# MercurialSDR_MISC.net
KiCad netlist of a schematic drawn in Altium Designer
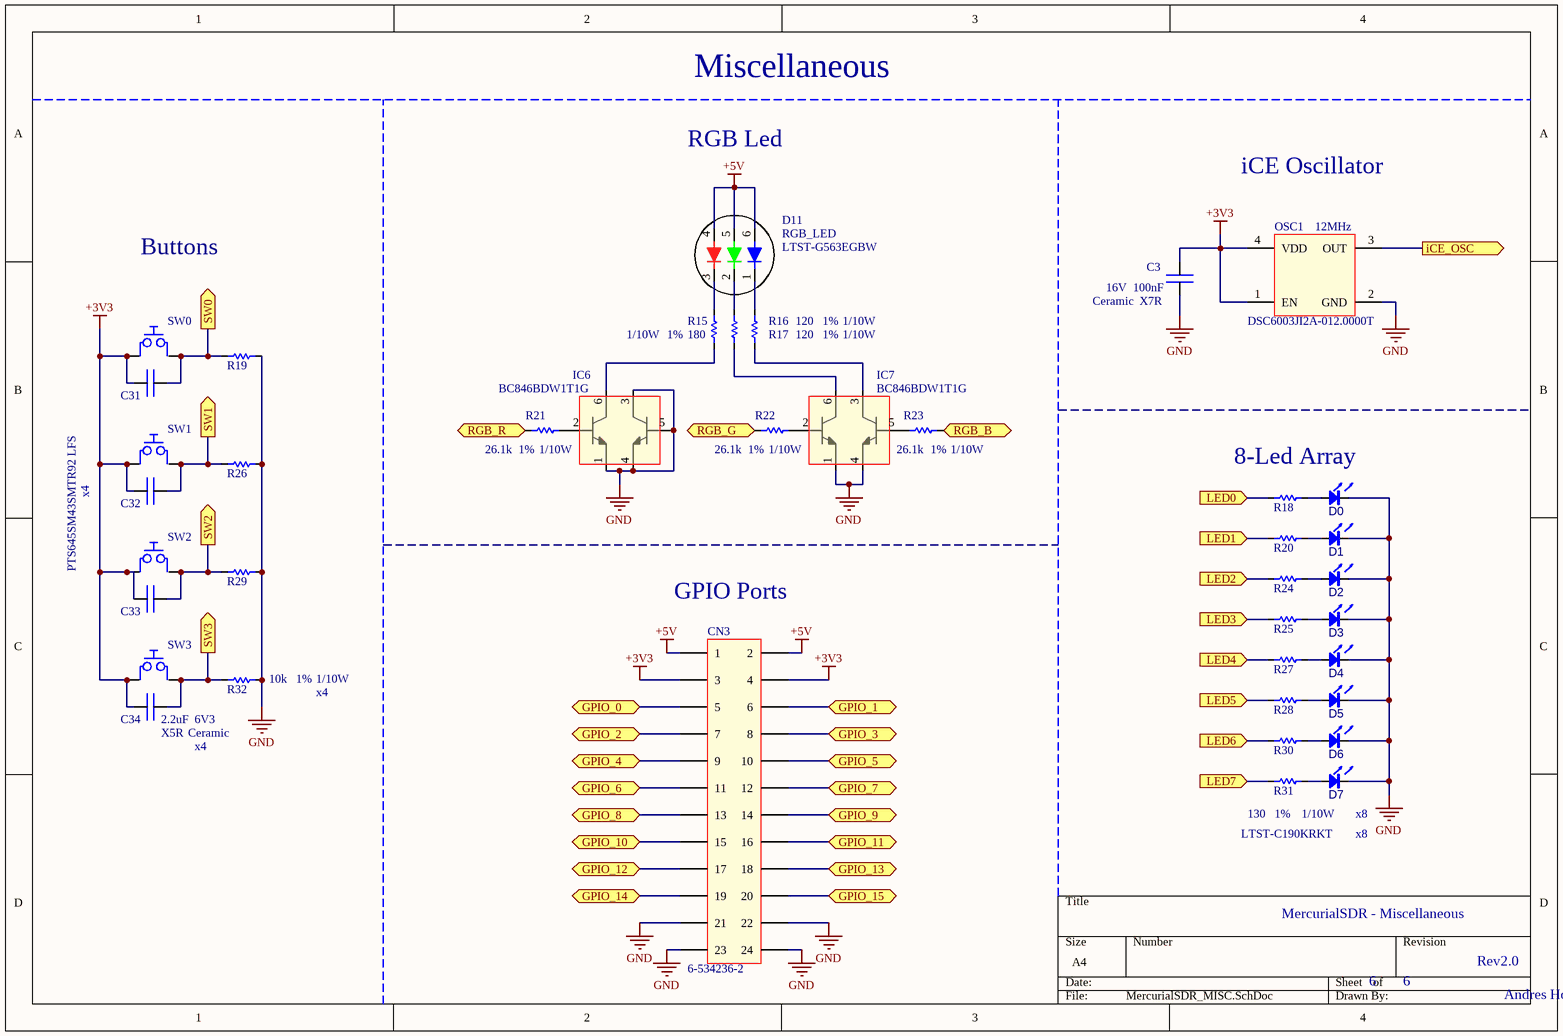
[diagram p0: MercurialSDR_MISC.SchDoc]

(export (version "E")
  (design (tool "Eeschema 10.0.6"))
  (components
    (comp (ref "C3")
      (value "100nF")
      (footprint "CAP_0603")
      (description "Capacitor no polarizado")
      (fields
        (field (name "TEMP COEF") "X7R")
        (field (name "PART NUMBER") "CL10B104KO8NNNC")
        (field (name "VR") "16V")
        (field (name "MATERIAL") "Ceramic")
        (field (name "Comment") "Capacitor")
      )
      (libsource (lib "MercurialSDR") (part "Cap"))
    )
    (comp (ref "C31")
      (value "Capacitor")
      (footprint "CAP_0603")
      (description "Capacitor no polarizado")
      (fields (field (name "PART NUMBER") "CL10A225KQ8NNNC"))
      (libsource (lib "MercurialSDR") (part "Cap"))
    )
    (comp (ref "C32")
      (value "Capacitor")
      (footprint "CAP_0603")
      (description "Capacitor no polarizado")
      (fields (field (name "PART NUMBER") "CL10A225KQ8NNNC"))
      (libsource (lib "MercurialSDR") (part "Cap"))
    )
    (comp (ref "C33")
      (value "Capacitor")
      (footprint "CAP_0603")
      (description "Capacitor no polarizado")
      (fields (field (name "PART NUMBER") "CL10A225KQ8NNNC"))
      (libsource (lib "MercurialSDR") (part "Cap"))
    )
    (comp (ref "C34")
      (value "2.2uF")
      (footprint "CAP_0603")
      (description "Capacitor no polarizado")
      (fields
        (field (name "TEMP COEF") "X5R")
        (field (name "PART NUMBER") "CL10A225KQ8NNNC")
        (field (name "VR") "6V3")
        (field (name "MATERIAL") "Ceramic")
        (field (name "Comment") "Capacitor")
      )
      (libsource (lib "MercurialSDR") (part "Cap"))
    )
    (comp (ref "CN3")
      (value "Connector")
      (footprint "CON_12x2")
      (description "Conector genérico 12x2")
      (fields (field (name "PART NUMBER") "6-534236-2"))
      (libsource (lib "MercurialSDR") (part "CN_12x2"))
    )
    (comp (ref "D0")
      (value "Led_small")
      (footprint "LED_0603")
      (fields (field (name "PART NUMBER") "LTST-C190KRKT"))
      (libsource (lib "MercurialSDR") (part "Led_small"))
    )
    (comp (ref "D1")
      (value "Led_small")
      (footprint "LED_0603")
      (fields (field (name "PART NUMBER") "LTST-C190KRKT"))
      (libsource (lib "MercurialSDR") (part "Led_small"))
    )
    (comp (ref "D2")
      (value "Led_small")
      (footprint "LED_0603")
      (fields (field (name "PART NUMBER") "LTST-C190KRKT"))
      (libsource (lib "MercurialSDR") (part "Led_small"))
    )
    (comp (ref "D3")
      (value "Led_small")
      (footprint "LED_0603")
      (fields (field (name "PART NUMBER") "LTST-C190KRKT"))
      (libsource (lib "MercurialSDR") (part "Led_small"))
    )
    (comp (ref "D4")
      (value "Led_small")
      (footprint "LED_0603")
      (fields (field (name "PART NUMBER") "LTST-C190KRKT"))
      (libsource (lib "MercurialSDR") (part "Led_small"))
    )
    (comp (ref "D5")
      (value "Led_small")
      (footprint "LED_0603")
      (fields (field (name "PART NUMBER") "LTST-C190KRKT"))
      (libsource (lib "MercurialSDR") (part "Led_small"))
    )
    (comp (ref "D6")
      (value "Led_small")
      (footprint "LED_0603")
      (fields (field (name "PART NUMBER") "LTST-C190KRKT"))
      (libsource (lib "MercurialSDR") (part "Led_small"))
    )
    (comp (ref "D7")
      (value "Led_small")
      (footprint "LED_0603")
      (fields (field (name "PART NUMBER") "LTST-C190KRKT"))
      (libsource (lib "MercurialSDR") (part "Led_small"))
    )
    (comp (ref "D11")
      (value "RGB_LED")
      (footprint "LED_RGB 5x5mm")
      (description "Led RGB")
      (fields (field (name "PART NUMBER") "LTST-G563EGBW"))
      (libsource (lib "MercurialSDR") (part "LED_RGB"))
    )
    (comp (ref "IC6")
      (value "BC846")
      (footprint "TSSOP-6")
      (description "TBJ NPN Dual")
      (fields (field (name "PART NUMBER") "BC846BDW1T1G"))
      (libsource (lib "MercurialSDR") (part "BC846BDW_1"))
    )
    (comp (ref "IC7")
      (value "BC846")
      (footprint "TSSOP-6")
      (description "TBJ NPN Dual")
      (fields (field (name "PART NUMBER") "BC846BDW1T1G"))
      (libsource (lib "MercurialSDR") (part "BC846BDW_1"))
    )
    (comp (ref "OSC1")
      (value "Oscillator")
      (footprint "VFLGA_2.5x2.0")
      (description "Oscilador de 4 terminales")
      (fields (field (name "PART NUMBER") "DSC6003JI2A-012.0000T") (field (name "FREQUENCY") "12MHz"))
      (libsource (lib "MercurialSDR") (part "Oscillator"))
    )
    (comp (ref "R15")
      (value "180")
      (footprint "RES_0603")
      (description "Resistor")
      (fields
        (field (name "POWER") "1/10W")
        (field (name "PART NUMBER") "CR0603-FX-1800ELF")
        (field (name "TOLERANCE") "1%")
        (field (name "Comment") "Resistor SMD")
      )
      (libsource (lib "MercurialSDR") (part "Res"))
    )
    (comp (ref "R16")
      (value "120")
      (footprint "RES_0603")
      (description "Resistor")
      (fields
        (field (name "POWER") "1/10W")
        (field (name "PART NUMBER") "CR0603-FX-1200ELF")
        (field (name "TOLERANCE") "1%")
        (field (name "Comment") "Resistor SMD")
      )
      (libsource (lib "MercurialSDR") (part "Res"))
    )
    (comp (ref "R17")
      (value "120")
      (footprint "RES_0603")
      (description "Resistor")
      (fields
        (field (name "POWER") "1/10W")
        (field (name "PART NUMBER") "CR0603-FX-1200ELF")
        (field (name "TOLERANCE") "1%")
        (field (name "Comment") "Resistor SMD")
      )
      (libsource (lib "MercurialSDR") (part "Res"))
    )
    (comp (ref "R18")
      (value "Resistor SMD")
      (footprint "RES_0603")
      (description "Resistor")
      (fields (field (name "POWER") "1/10W") (field (name "PART NUMBER") "CR0603-FX-1300ELF"))
      (libsource (lib "MercurialSDR") (part "Res"))
    )
    (comp (ref "R19")
      (value "10k")
      (footprint "RES_0603")
      (description "Resistor")
      (fields
        (field (name "POWER") "1/10W")
        (field (name "PART NUMBER") "CR0603-FX-1002EAS")
        (field (name "TOLERANCE") "1%")
        (field (name "Comment") "Resistor SMD")
      )
      (libsource (lib "MercurialSDR") (part "Res"))
    )
    (comp (ref "R20")
      (value "Resistor SMD")
      (footprint "RES_0603")
      (description "Resistor")
      (fields (field (name "POWER") "1/10W") (field (name "PART NUMBER") "CR0603-FX-1300ELF"))
      (libsource (lib "MercurialSDR") (part "Res"))
    )
    (comp (ref "R21")
      (value "26.1k")
      (footprint "RES_0603")
      (description "Resistor")
      (fields
        (field (name "POWER") "1/10W")
        (field (name "PART NUMBER") "CR0603-FX-2612ELF")
        (field (name "TOLERANCE") "1%")
        (field (name "Comment") "Resistor SMD")
      )
      (libsource (lib "MercurialSDR") (part "Res"))
    )
    (comp (ref "R22")
      (value "26.1k")
      (footprint "RES_0603")
      (description "Resistor")
      (fields
        (field (name "POWER") "1/10W")
        (field (name "PART NUMBER") "CR0603-FX-2612ELF")
        (field (name "TOLERANCE") "1%")
        (field (name "Comment") "Resistor SMD")
      )
      (libsource (lib "MercurialSDR") (part "Res"))
    )
    (comp (ref "R23")
      (value "26.1k")
      (footprint "RES_0603")
      (description "Resistor")
      (fields
        (field (name "POWER") "1/10W")
        (field (name "PART NUMBER") "CR0603-FX-2612ELF")
        (field (name "TOLERANCE") "1%")
        (field (name "Comment") "Resistor SMD")
      )
      (libsource (lib "MercurialSDR") (part "Res"))
    )
    (comp (ref "R24")
      (value "Resistor SMD")
      (footprint "RES_0603")
      (description "Resistor")
      (fields (field (name "POWER") "1/10W") (field (name "PART NUMBER") "CR0603-FX-1300ELF"))
      (libsource (lib "MercurialSDR") (part "Res"))
    )
    (comp (ref "R25")
      (value "Resistor SMD")
      (footprint "RES_0603")
      (description "Resistor")
      (fields (field (name "POWER") "1/10W") (field (name "PART NUMBER") "CR0603-FX-1300ELF"))
      (libsource (lib "MercurialSDR") (part "Res"))
    )
    (comp (ref "R26")
      (value "Resistor SMD")
      (footprint "RES_0603")
      (description "Resistor")
      (fields (field (name "POWER") "1/10W") (field (name "PART NUMBER") "CR0603-FX-1002EAS"))
      (libsource (lib "MercurialSDR") (part "Res"))
    )
    (comp (ref "R27")
      (value "Resistor SMD")
      (footprint "RES_0603")
      (description "Resistor")
      (fields (field (name "POWER") "1/10W") (field (name "PART NUMBER") "CR0603-FX-1300ELF"))
      (libsource (lib "MercurialSDR") (part "Res"))
    )
    (comp (ref "R28")
      (value "Resistor SMD")
      (footprint "RES_0603")
      (description "Resistor")
      (fields (field (name "POWER") "1/10W") (field (name "PART NUMBER") "CR0603-FX-1300ELF"))
      (libsource (lib "MercurialSDR") (part "Res"))
    )
    (comp (ref "R29")
      (value "Resistor SMD")
      (footprint "RES_0603")
      (description "Resistor")
      (fields (field (name "POWER") "1/10W") (field (name "PART NUMBER") "CR0603-FX-1002EAS"))
      (libsource (lib "MercurialSDR") (part "Res"))
    )
    (comp (ref "R30")
      (value "Resistor SMD")
      (footprint "RES_0603")
      (description "Resistor")
      (fields (field (name "POWER") "1/10W") (field (name "PART NUMBER") "CR0603-FX-1300ELF"))
      (libsource (lib "MercurialSDR") (part "Res"))
    )
    (comp (ref "R31")
      (value "130")
      (footprint "RES_0603")
      (description "Resistor")
      (fields
        (field (name "POWER") "1/10W")
        (field (name "PART NUMBER") "CR0603-FX-1300ELF")
        (field (name "TOLERANCE") "1%")
        (field (name "Comment") "Resistor SMD")
      )
      (libsource (lib "MercurialSDR") (part "Res"))
    )
    (comp (ref "R32")
      (value "Resistor SMD")
      (footprint "RES_0603")
      (description "Resistor")
      (fields (field (name "POWER") "1/10W") (field (name "PART NUMBER") "CR0603-FX-1002EAS"))
      (libsource (lib "MercurialSDR") (part "Res"))
    )
    (comp (ref "SW0")
      (value "Pulsador")
      (footprint "SWITCH_6X6mm")
      (fields (field (name "PART NUMBER") "PTS645SM43SMTR92 LFS"))
      (libsource (lib "MercurialSDR") (part "Pulsador"))
    )
    (comp (ref "SW1")
      (value "Pulsador")
      (footprint "SWITCH_6X6mm")
      (fields (field (name "PART NUMBER") "PTS645SM43SMTR92 LFS"))
      (libsource (lib "MercurialSDR") (part "Pulsador"))
    )
    (comp (ref "SW2")
      (value "Pulsador")
      (footprint "SWITCH_6X6mm")
      (fields (field (name "PART NUMBER") "PTS645SM43SMTR92 LFS"))
      (libsource (lib "MercurialSDR") (part "Pulsador"))
    )
    (comp (ref "SW3")
      (value "Pulsador")
      (footprint "SWITCH_6X6mm")
      (fields (field (name "PART NUMBER") "PTS645SM43SMTR92 LFS"))
      (libsource (lib "MercurialSDR") (part "Pulsador"))
    )
  )
  (nets
    (net (code "1") (name "+3V3") (class "Default")
      (node (ref "C3") (pin "1") (pinfunction "1_1") (pintype "passive"))
      (node (ref "C31") (pin "1") (pinfunction "1_1") (pintype "passive"))
      (node (ref "C32") (pin "1") (pinfunction "1_1") (pintype "passive"))
      (node (ref "C33") (pin "1") (pinfunction "1_1") (pintype "passive"))
      (node (ref "C34") (pin "1") (pinfunction "1_1") (pintype "passive"))
      (node (ref "CN3") (pin "3") (pinfunction "3_3") (pintype "passive"))
      (node (ref "CN3") (pin "4") (pinfunction "4_4") (pintype "passive"))
      (node (ref "OSC1") (pin "1") (pinfunction "EN_1") (pintype "passive"))
      (node (ref "OSC1") (pin "4") (pinfunction "VDD_4") (pintype "passive"))
      (node (ref "SW0") (pin "1") (pinfunction "1_1") (pintype "passive"))
      (node (ref "SW1") (pin "1") (pinfunction "1_1") (pintype "passive"))
      (node (ref "SW2") (pin "1") (pinfunction "1_1") (pintype "passive"))
      (node (ref "SW3") (pin "1") (pinfunction "1_1") (pintype "passive"))
    )
    (net (code "2") (name "+5V") (class "Default")
      (node (ref "CN3") (pin "1") (pinfunction "1_1") (pintype "passive"))
      (node (ref "CN3") (pin "2") (pinfunction "2_2") (pintype "passive"))
      (node (ref "D11") (pin "4") (pinfunction "RA_4") (pintype "passive"))
      (node (ref "D11") (pin "5") (pinfunction "GA_5") (pintype "passive"))
      (node (ref "D11") (pin "6") (pinfunction "BA_6") (pintype "passive"))
    )
    (net (code "3") (name "/GPIO_0") (class "Default")
      (node (ref "CN3") (pin "5") (pinfunction "5_5") (pintype "passive"))
    )
    (net (code "4") (name "/GPIO_1") (class "Default")
      (node (ref "CN3") (pin "6") (pinfunction "6_6") (pintype "passive"))
    )
    (net (code "5") (name "/GPIO_2") (class "Default")
      (node (ref "CN3") (pin "7") (pinfunction "7_7") (pintype "passive"))
    )
    (net (code "6") (name "/GPIO_3") (class "Default")
      (node (ref "CN3") (pin "8") (pinfunction "8_8") (pintype "passive"))
    )
    (net (code "7") (name "/GPIO_4") (class "Default")
      (node (ref "CN3") (pin "9") (pinfunction "9_9") (pintype "passive"))
    )
    (net (code "8") (name "/GPIO_5") (class "Default")
      (node (ref "CN3") (pin "10") (pinfunction "10_10") (pintype "passive"))
    )
    (net (code "9") (name "/GPIO_6") (class "Default")
      (node (ref "CN3") (pin "11") (pinfunction "11_11") (pintype "passive"))
    )
    (net (code "10") (name "/GPIO_7") (class "Default")
      (node (ref "CN3") (pin "12") (pinfunction "12_12") (pintype "passive"))
    )
    (net (code "11") (name "/GPIO_8") (class "Default")
      (node (ref "CN3") (pin "13") (pinfunction "13_13") (pintype "passive"))
    )
    (net (code "12") (name "/GPIO_9") (class "Default")
      (node (ref "CN3") (pin "14") (pinfunction "14_14") (pintype "passive"))
    )
    (net (code "13") (name "/GPIO_10") (class "Default")
      (node (ref "CN3") (pin "15") (pinfunction "15_15") (pintype "passive"))
    )
    (net (code "14") (name "/GPIO_11") (class "Default")
      (node (ref "CN3") (pin "16") (pinfunction "16_16") (pintype "passive"))
    )
    (net (code "15") (name "/GPIO_12") (class "Default")
      (node (ref "CN3") (pin "17") (pinfunction "17_17") (pintype "passive"))
    )
    (net (code "16") (name "/GPIO_13") (class "Default")
      (node (ref "CN3") (pin "18") (pinfunction "18_18") (pintype "passive"))
    )
    (net (code "17") (name "/GPIO_14") (class "Default")
      (node (ref "CN3") (pin "19") (pinfunction "19_19") (pintype "passive"))
    )
    (net (code "18") (name "/GPIO_15") (class "Default")
      (node (ref "CN3") (pin "20") (pinfunction "20_20") (pintype "passive"))
    )
    (net (code "19") (name "/LED0") (class "Default")
      (node (ref "R18") (pin "2") (pinfunction "2_2") (pintype "passive"))
    )
    (net (code "20") (name "/LED1") (class "Default")
      (node (ref "R20") (pin "2") (pinfunction "2_2") (pintype "passive"))
    )
    (net (code "21") (name "/LED2") (class "Default")
      (node (ref "R24") (pin "2") (pinfunction "2_2") (pintype "passive"))
    )
    (net (code "22") (name "/LED3") (class "Default")
      (node (ref "R25") (pin "2") (pinfunction "2_2") (pintype "passive"))
    )
    (net (code "23") (name "/LED4") (class "Default")
      (node (ref "R27") (pin "2") (pinfunction "2_2") (pintype "passive"))
    )
    (net (code "24") (name "/LED5") (class "Default")
      (node (ref "R28") (pin "2") (pinfunction "2_2") (pintype "passive"))
    )
    (net (code "25") (name "/LED6") (class "Default")
      (node (ref "R30") (pin "2") (pinfunction "2_2") (pintype "passive"))
    )
    (net (code "26") (name "/LED7") (class "Default")
      (node (ref "R31") (pin "2") (pinfunction "2_2") (pintype "passive"))
    )
    (net (code "27") (name "/RGB_B") (class "Default")
      (node (ref "R23") (pin "1") (pinfunction "1_1") (pintype "passive"))
    )
    (net (code "28") (name "/RGB_G") (class "Default")
      (node (ref "R22") (pin "2") (pinfunction "2_2") (pintype "passive"))
    )
    (net (code "29") (name "/RGB_R") (class "Default")
      (node (ref "R21") (pin "2") (pinfunction "2_2") (pintype "passive"))
    )
    (net (code "30") (name "/SW0") (class "Default")
      (node (ref "C31") (pin "2") (pinfunction "2_2") (pintype "passive"))
      (node (ref "R19") (pin "2") (pinfunction "2_2") (pintype "passive"))
      (node (ref "SW0") (pin "4") (pinfunction "4_4") (pintype "passive"))
    )
    (net (code "31") (name "/SW1") (class "Default")
      (node (ref "C32") (pin "2") (pinfunction "2_2") (pintype "passive"))
      (node (ref "R26") (pin "2") (pinfunction "2_2") (pintype "passive"))
      (node (ref "SW1") (pin "4") (pinfunction "4_4") (pintype "passive"))
    )
    (net (code "32") (name "/SW2") (class "Default")
      (node (ref "C33") (pin "2") (pinfunction "2_2") (pintype "passive"))
      (node (ref "R29") (pin "2") (pinfunction "2_2") (pintype "passive"))
      (node (ref "SW2") (pin "4") (pinfunction "4_4") (pintype "passive"))
    )
    (net (code "33") (name "/SW3") (class "Default")
      (node (ref "C34") (pin "2") (pinfunction "2_2") (pintype "passive"))
      (node (ref "R32") (pin "2") (pinfunction "2_2") (pintype "passive"))
      (node (ref "SW3") (pin "4") (pinfunction "4_4") (pintype "passive"))
    )
    (net (code "34") (name "/iCE_OSC") (class "Default")
      (node (ref "OSC1") (pin "3") (pinfunction "OUT_3") (pintype "passive"))
    )
    (net (code "35") (name "GND") (class "Default")
      (node (ref "C3") (pin "2") (pinfunction "2_2") (pintype "passive"))
      (node (ref "CN3") (pin "21") (pinfunction "21_21") (pintype "passive"))
      (node (ref "CN3") (pin "22") (pinfunction "22_22") (pintype "passive"))
      (node (ref "CN3") (pin "23") (pinfunction "23_23") (pintype "passive"))
      (node (ref "CN3") (pin "24") (pinfunction "24_24") (pintype "passive"))
      (node (ref "D0") (pin "2") (pinfunction "K_2") (pintype "passive"))
      (node (ref "D1") (pin "2") (pinfunction "K_2") (pintype "passive"))
      (node (ref "D2") (pin "2") (pinfunction "K_2") (pintype "passive"))
      (node (ref "D3") (pin "2") (pinfunction "K_2") (pintype "passive"))
      (node (ref "D4") (pin "2") (pinfunction "K_2") (pintype "passive"))
      (node (ref "D5") (pin "2") (pinfunction "K_2") (pintype "passive"))
      (node (ref "D6") (pin "2") (pinfunction "K_2") (pintype "passive"))
      (node (ref "D7") (pin "2") (pinfunction "K_2") (pintype "passive"))
      (node (ref "IC6") (pin "1") (pinfunction "E_1_1") (pintype "passive"))
      (node (ref "IC6") (pin "3") (pinfunction "C_2_3") (pintype "passive"))
      (node (ref "IC6") (pin "4") (pinfunction "E_2_4") (pintype "passive"))
      (node (ref "IC6") (pin "5") (pinfunction "B_2_5") (pintype "passive"))
      (node (ref "IC7") (pin "1") (pinfunction "E_1_1") (pintype "passive"))
      (node (ref "IC7") (pin "4") (pinfunction "E_2_4") (pintype "passive"))
      (node (ref "OSC1") (pin "2") (pinfunction "GND_2") (pintype "passive"))
      (node (ref "R19") (pin "1") (pinfunction "1_1") (pintype "passive"))
      (node (ref "R26") (pin "1") (pinfunction "1_1") (pintype "passive"))
      (node (ref "R29") (pin "1") (pinfunction "1_1") (pintype "passive"))
      (node (ref "R32") (pin "1") (pinfunction "1_1") (pintype "passive"))
    )
    (net (code "36") (name "Net-(D0-A)") (class "Default")
      (node (ref "D0") (pin "1") (pinfunction "A_1") (pintype "passive"))
      (node (ref "R18") (pin "1") (pinfunction "1_1") (pintype "passive"))
    )
    (net (code "37") (name "Net-(D1-A)") (class "Default")
      (node (ref "D1") (pin "1") (pinfunction "A_1") (pintype "passive"))
      (node (ref "R20") (pin "1") (pinfunction "1_1") (pintype "passive"))
    )
    (net (code "38") (name "Net-(D2-A)") (class "Default")
      (node (ref "D2") (pin "1") (pinfunction "A_1") (pintype "passive"))
      (node (ref "R24") (pin "1") (pinfunction "1_1") (pintype "passive"))
    )
    (net (code "39") (name "Net-(D3-A)") (class "Default")
      (node (ref "D3") (pin "1") (pinfunction "A_1") (pintype "passive"))
      (node (ref "R25") (pin "1") (pinfunction "1_1") (pintype "passive"))
    )
    (net (code "40") (name "Net-(D4-A)") (class "Default")
      (node (ref "D4") (pin "1") (pinfunction "A_1") (pintype "passive"))
      (node (ref "R27") (pin "1") (pinfunction "1_1") (pintype "passive"))
    )
    (net (code "41") (name "Net-(D5-A)") (class "Default")
      (node (ref "D5") (pin "1") (pinfunction "A_1") (pintype "passive"))
      (node (ref "R28") (pin "1") (pinfunction "1_1") (pintype "passive"))
    )
    (net (code "42") (name "Net-(D6-A)") (class "Default")
      (node (ref "D6") (pin "1") (pinfunction "A_1") (pintype "passive"))
      (node (ref "R30") (pin "1") (pinfunction "1_1") (pintype "passive"))
    )
    (net (code "43") (name "Net-(D7-A)") (class "Default")
      (node (ref "D7") (pin "1") (pinfunction "A_1") (pintype "passive"))
      (node (ref "R31") (pin "1") (pinfunction "1_1") (pintype "passive"))
    )
    (net (code "44") (name "Net-(D11-BK)") (class "Default")
      (node (ref "D11") (pin "1") (pinfunction "BK_1") (pintype "passive"))
      (node (ref "R17") (pin "1") (pinfunction "1_1") (pintype "passive"))
    )
    (net (code "45") (name "Net-(D11-GK)") (class "Default")
      (node (ref "D11") (pin "2") (pinfunction "GK_2") (pintype "passive"))
      (node (ref "R16") (pin "1") (pinfunction "1_1") (pintype "passive"))
    )
    (net (code "46") (name "Net-(D11-RK)") (class "Default")
      (node (ref "D11") (pin "3") (pinfunction "RK_3") (pintype "passive"))
      (node (ref "R15") (pin "1") (pinfunction "1_1") (pintype "passive"))
    )
    (net (code "47") (name "Net-(IC6-B_1)") (class "Default")
      (node (ref "IC6") (pin "2") (pinfunction "B_1_2") (pintype "passive"))
      (node (ref "R21") (pin "1") (pinfunction "1_1") (pintype "passive"))
    )
    (net (code "48") (name "Net-(IC6-C_1)") (class "Default")
      (node (ref "IC6") (pin "6") (pinfunction "C_1_6") (pintype "passive"))
      (node (ref "R15") (pin "2") (pinfunction "2_2") (pintype "passive"))
    )
    (net (code "49") (name "Net-(IC7-B_1)") (class "Default")
      (node (ref "IC7") (pin "2") (pinfunction "B_1_2") (pintype "passive"))
      (node (ref "R22") (pin "1") (pinfunction "1_1") (pintype "passive"))
    )
    (net (code "50") (name "Net-(IC7-B_2)") (class "Default")
      (node (ref "IC7") (pin "5") (pinfunction "B_2_5") (pintype "passive"))
      (node (ref "R23") (pin "2") (pinfunction "2_2") (pintype "passive"))
    )
    (net (code "51") (name "Net-(IC7-C_1)") (class "Default")
      (node (ref "IC7") (pin "6") (pinfunction "C_1_6") (pintype "passive"))
      (node (ref "R16") (pin "2") (pinfunction "2_2") (pintype "passive"))
    )
    (net (code "52") (name "Net-(IC7-C_2)") (class "Default")
      (node (ref "IC7") (pin "3") (pinfunction "C_2_3") (pintype "passive"))
      (node (ref "R17") (pin "2") (pinfunction "2_2") (pintype "passive"))
    )
    (net (code "53") (name "unconnected-(SW0-Pad2)") (class "Default")
      (node (ref "SW0") (pin "2") (pinfunction "2_2") (pintype "passive"))
    )
    (net (code "54") (name "unconnected-(SW0-Pad3)") (class "Default")
      (node (ref "SW0") (pin "3") (pinfunction "3_3") (pintype "passive"))
    )
    (net (code "55") (name "unconnected-(SW1-Pad2)") (class "Default")
      (node (ref "SW1") (pin "2") (pinfunction "2_2") (pintype "passive"))
    )
    (net (code "56") (name "unconnected-(SW1-Pad3)") (class "Default")
      (node (ref "SW1") (pin "3") (pinfunction "3_3") (pintype "passive"))
    )
    (net (code "57") (name "unconnected-(SW2-Pad2)") (class "Default")
      (node (ref "SW2") (pin "2") (pinfunction "2_2") (pintype "passive"))
    )
    (net (code "58") (name "unconnected-(SW2-Pad3)") (class "Default")
      (node (ref "SW2") (pin "3") (pinfunction "3_3") (pintype "passive"))
    )
    (net (code "59") (name "unconnected-(SW3-Pad2)") (class "Default")
      (node (ref "SW3") (pin "2") (pinfunction "2_2") (pintype "passive"))
    )
    (net (code "60") (name "unconnected-(SW3-Pad3)") (class "Default")
      (node (ref "SW3") (pin "3") (pinfunction "3_3") (pintype "passive"))
    )
  )
)
